# Conn_C.net
KiCad netlist of a schematic drawn in Altium Designer
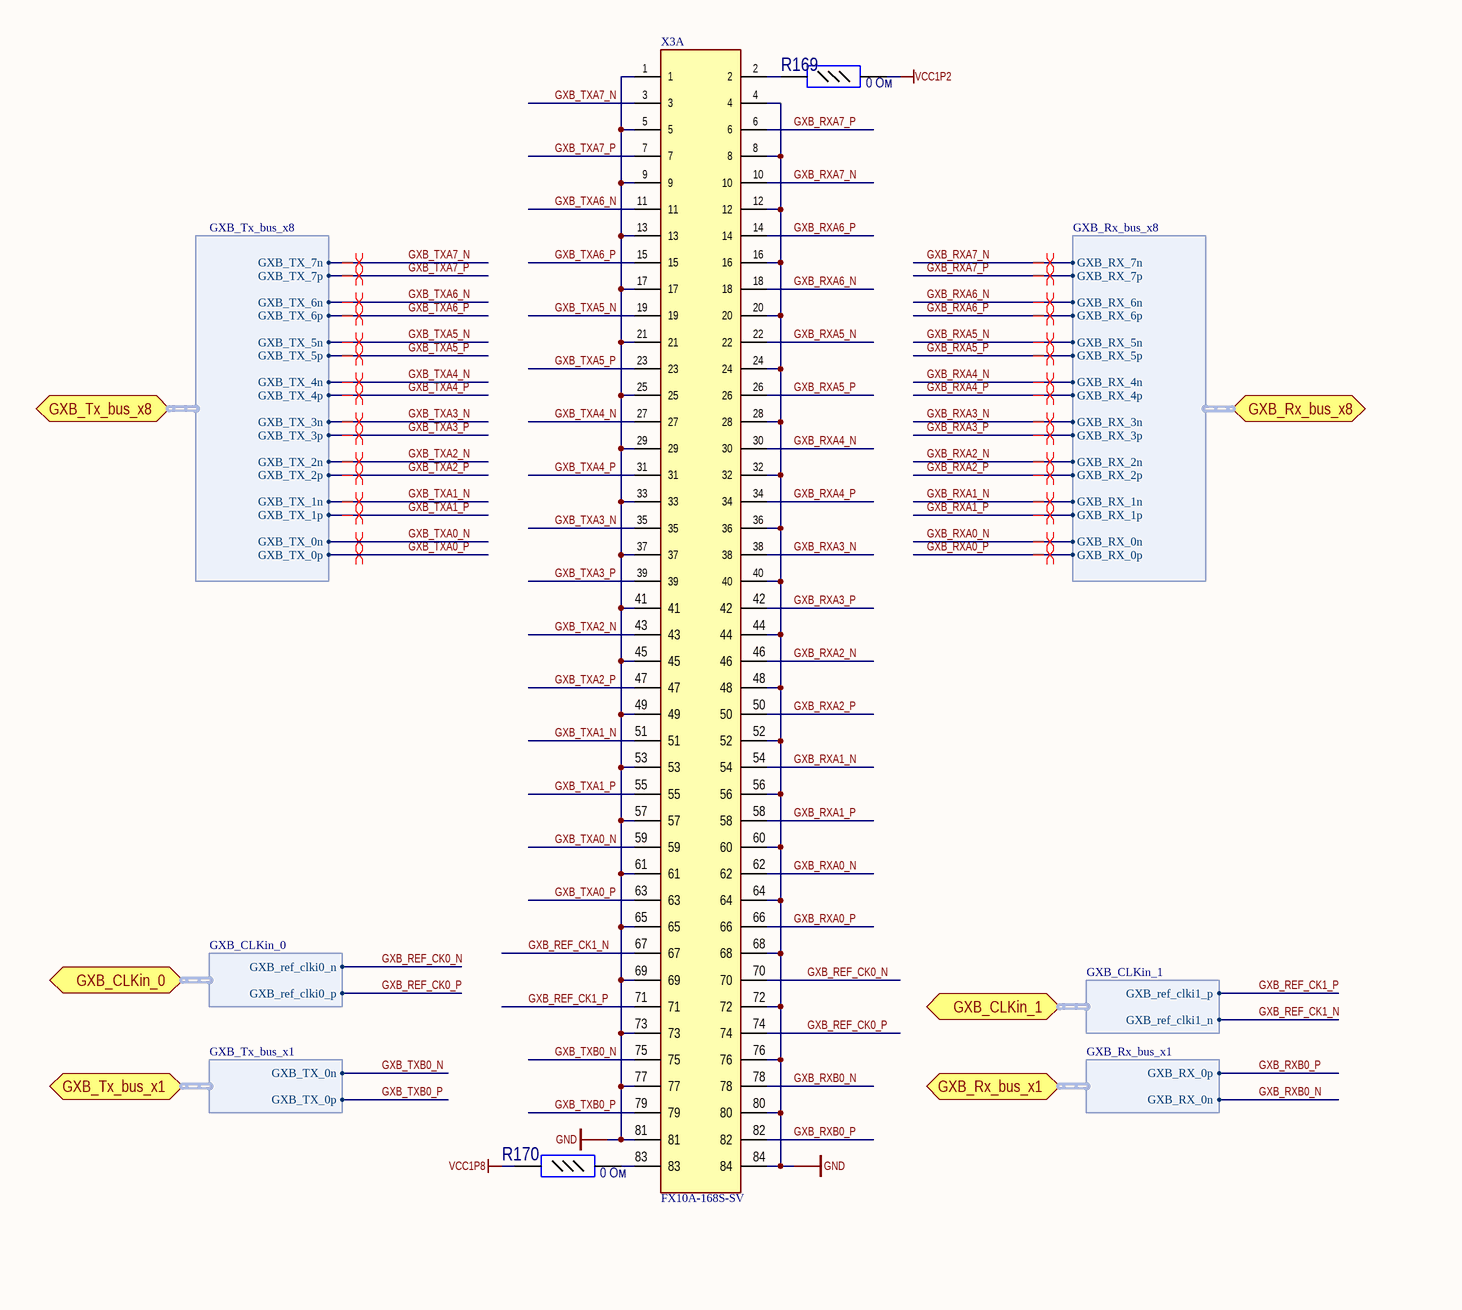
[diagram p0: Conn_C.SchDoc, left]
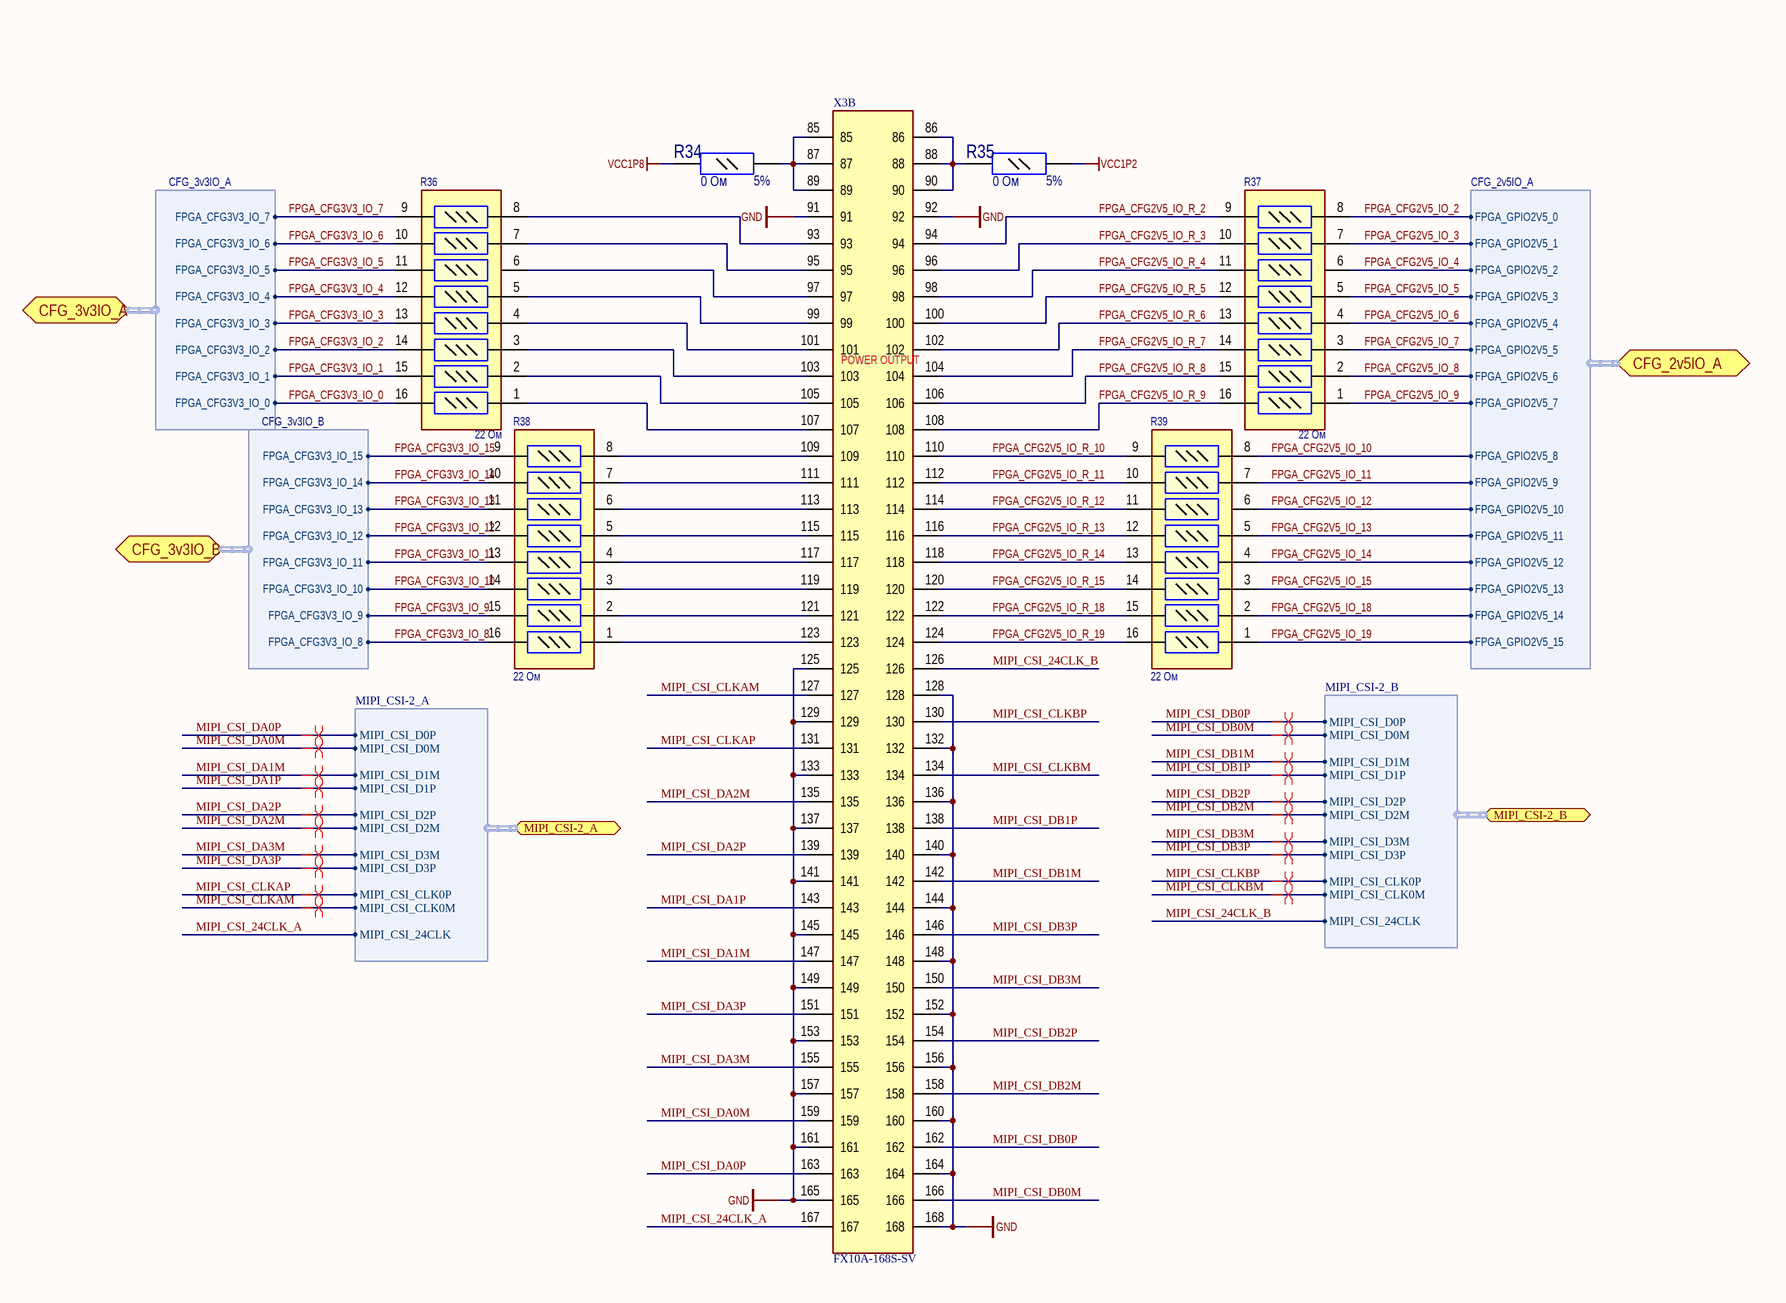
[diagram p1: Conn_C.SchDoc, right]

(export (version "E")
  (design (tool "Eeschema 10.0.6"))
  (components
    (comp (ref "R34")
      (value "0 Ом")
      (footprint "CR0805")
      (description "Чип резистор")
      (fields (field (name "TOLERANCE") "5%") (field (name "Comment") "CR0805-0 Ом-±5%"))
      (libsource (lib "Резисторы") (part "CR0805-#-±1%"))
    )
    (comp (ref "R35")
      (value "0 Ом")
      (footprint "CR0805")
      (description "Чип резистор")
      (fields (field (name "TOLERANCE") "5%") (field (name "Comment") "CR0805-0 Ом-±5%"))
      (libsource (lib "Резисторы") (part "CR0805-#-±1%"))
    )
    (comp (ref "R36")
      (value "22 Ом")
      (footprint "CAT16-J8")
      (description "Набор чип резисторов")
      (fields (field (name "Comment") "YC248-JR-07-22 Ом"))
      (libsource (lib "SD_IC") (part "YC248-JR-07-#"))
    )
    (comp (ref "R37")
      (value "22 Ом")
      (footprint "CAT16-J8")
      (description "Набор чип резисторов")
      (fields (field (name "Comment") "YC248-JR-07-22 Ом"))
      (libsource (lib "SD_IC") (part "YC248-JR-07-#"))
    )
    (comp (ref "R38")
      (value "22 Ом")
      (footprint "CAT16-J8")
      (description "Набор чип резисторов")
      (fields (field (name "Comment") "YC248-JR-07-22 Ом"))
      (libsource (lib "SD_IC") (part "YC248-JR-07-#"))
    )
    (comp (ref "R39")
      (value "22 Ом")
      (footprint "CAT16-J8")
      (description "Набор чип резисторов")
      (fields (field (name "Comment") "YC248-JR-07-22 Ом"))
      (libsource (lib "SD_IC") (part "YC248-JR-07-#"))
    )
    (comp (ref "R169")
      (value "0 Ом")
      (footprint "CR0603")
      (description "Чип резистор")
      (fields (field (name "Comment") "CR0603-0 Ом-±5%"))
      (libsource (lib "Резисторы") (part "CR0603-#-±5%"))
    )
    (comp (ref "R170")
      (value "0 Ом")
      (footprint "CR0603")
      (description "Чип резистор")
      (fields (field (name "Comment") "CR0603-0 Ом-±5%"))
      (libsource (lib "Резисторы") (part "CR0603-#-±5%"))
    )
    (comp (ref "X3")
      (value "FX10A-168S-SV")
      (footprint "FX10A-168S-SV")
      (libsource (lib "SD_IC") (part "FX10A-168S-SV"))
    )
  )
  (nets
    (net (code "12") (name "/FPGA_CFG2V5_IO_2") (class "Default")
      (node (ref "R37") (pin "8") (pintype "passive"))
    )
    (net (code "13") (name "/FPGA_CFG2V5_IO_3") (class "Default")
      (node (ref "R37") (pin "7") (pintype "passive"))
    )
    (net (code "14") (name "/FPGA_CFG2V5_IO_4") (class "Default")
      (node (ref "R37") (pin "6") (pintype "passive"))
    )
    (net (code "15") (name "/FPGA_CFG2V5_IO_5") (class "Default")
      (node (ref "R37") (pin "5") (pintype "passive"))
    )
    (net (code "16") (name "/FPGA_CFG2V5_IO_6") (class "Default")
      (node (ref "R37") (pin "4") (pintype "passive"))
    )
    (net (code "17") (name "/FPGA_CFG2V5_IO_7") (class "Default")
      (node (ref "R37") (pin "3") (pintype "passive"))
    )
    (net (code "18") (name "/FPGA_CFG2V5_IO_8") (class "Default")
      (node (ref "R37") (pin "2") (pintype "passive"))
    )
    (net (code "19") (name "/FPGA_CFG2V5_IO_9") (class "Default")
      (node (ref "R37") (pin "1") (pintype "passive"))
    )
    (net (code "20") (name "/FPGA_CFG2V5_IO_10") (class "Default")
      (node (ref "R39") (pin "8") (pintype "passive"))
    )
    (net (code "21") (name "/FPGA_CFG2V5_IO_11") (class "Default")
      (node (ref "R39") (pin "7") (pintype "passive"))
    )
    (net (code "22") (name "/FPGA_CFG2V5_IO_12") (class "Default")
      (node (ref "R39") (pin "6") (pintype "passive"))
    )
    (net (code "23") (name "/FPGA_CFG2V5_IO_13") (class "Default")
      (node (ref "R39") (pin "5") (pintype "passive"))
    )
    (net (code "24") (name "/FPGA_CFG2V5_IO_14") (class "Default")
      (node (ref "R39") (pin "4") (pintype "passive"))
    )
    (net (code "25") (name "/FPGA_CFG2V5_IO_15") (class "Default")
      (node (ref "R39") (pin "3") (pintype "passive"))
    )
    (net (code "26") (name "/FPGA_CFG2V5_IO_18") (class "Default")
      (node (ref "R39") (pin "2") (pintype "passive"))
    )
    (net (code "27") (name "/FPGA_CFG2V5_IO_19") (class "Default")
      (node (ref "R39") (pin "1") (pintype "passive"))
    )
    (net (code "28") (name "/FPGA_CFG2V5_IO_R_2") (class "Default")
      (node (ref "R37") (pin "9") (pintype "passive"))
      (node (ref "X3") (pin "94") (pinfunction "94_94") (pintype "passive"))
    )
    (net (code "29") (name "/FPGA_CFG2V5_IO_R_3") (class "Default")
      (node (ref "R37") (pin "10") (pintype "passive"))
      (node (ref "X3") (pin "96") (pinfunction "96_96") (pintype "passive"))
    )
    (net (code "30") (name "/FPGA_CFG2V5_IO_R_4") (class "Default")
      (node (ref "R37") (pin "11") (pintype "passive"))
      (node (ref "X3") (pin "98") (pinfunction "98_98") (pintype "passive"))
    )
    (net (code "31") (name "/FPGA_CFG2V5_IO_R_5") (class "Default")
      (node (ref "R37") (pin "12") (pintype "passive"))
      (node (ref "X3") (pin "100") (pinfunction "100_100") (pintype "passive"))
    )
    (net (code "32") (name "/FPGA_CFG2V5_IO_R_6") (class "Default")
      (node (ref "R37") (pin "13") (pintype "passive"))
      (node (ref "X3") (pin "102") (pinfunction "102_102") (pintype "passive"))
    )
    (net (code "33") (name "/FPGA_CFG2V5_IO_R_7") (class "Default")
      (node (ref "R37") (pin "14") (pintype "passive"))
      (node (ref "X3") (pin "104") (pinfunction "104_104") (pintype "passive"))
    )
    (net (code "34") (name "/FPGA_CFG2V5_IO_R_8") (class "Default")
      (node (ref "R37") (pin "15") (pintype "passive"))
      (node (ref "X3") (pin "106") (pinfunction "106_106") (pintype "passive"))
    )
    (net (code "35") (name "/FPGA_CFG2V5_IO_R_9") (class "Default")
      (node (ref "R37") (pin "16") (pintype "passive"))
      (node (ref "X3") (pin "108") (pinfunction "108_108") (pintype "passive"))
    )
    (net (code "36") (name "/FPGA_CFG2V5_IO_R_10") (class "Default")
      (node (ref "R39") (pin "9") (pintype "passive"))
      (node (ref "X3") (pin "110") (pinfunction "110_110") (pintype "passive"))
    )
    (net (code "37") (name "/FPGA_CFG2V5_IO_R_11") (class "Default")
      (node (ref "R39") (pin "10") (pintype "passive"))
      (node (ref "X3") (pin "112") (pinfunction "112_112") (pintype "passive"))
    )
    (net (code "38") (name "/FPGA_CFG2V5_IO_R_12") (class "Default")
      (node (ref "R39") (pin "11") (pintype "passive"))
      (node (ref "X3") (pin "114") (pinfunction "114_114") (pintype "passive"))
    )
    (net (code "39") (name "/FPGA_CFG2V5_IO_R_13") (class "Default")
      (node (ref "R39") (pin "12") (pintype "passive"))
      (node (ref "X3") (pin "116") (pinfunction "116_116") (pintype "passive"))
    )
    (net (code "40") (name "/FPGA_CFG2V5_IO_R_14") (class "Default")
      (node (ref "R39") (pin "13") (pintype "passive"))
      (node (ref "X3") (pin "118") (pinfunction "118_118") (pintype "passive"))
    )
    (net (code "41") (name "/FPGA_CFG2V5_IO_R_15") (class "Default")
      (node (ref "R39") (pin "14") (pintype "passive"))
      (node (ref "X3") (pin "120") (pinfunction "120_120") (pintype "passive"))
    )
    (net (code "42") (name "/FPGA_CFG2V5_IO_R_18") (class "Default")
      (node (ref "R39") (pin "15") (pintype "passive"))
      (node (ref "X3") (pin "122") (pinfunction "122_122") (pintype "passive"))
    )
    (net (code "43") (name "/FPGA_CFG2V5_IO_R_19") (class "Default")
      (node (ref "R39") (pin "16") (pintype "passive"))
      (node (ref "X3") (pin "124") (pinfunction "124_124") (pintype "passive"))
    )
    (net (code "44") (name "/FPGA_CFG3V3_IO_0") (class "Default")
      (node (ref "R36") (pin "16") (pintype "passive"))
    )
    (net (code "45") (name "/FPGA_CFG3V3_IO_1") (class "Default")
      (node (ref "R36") (pin "15") (pintype "passive"))
    )
    (net (code "46") (name "/FPGA_CFG3V3_IO_2") (class "Default")
      (node (ref "R36") (pin "14") (pintype "passive"))
    )
    (net (code "47") (name "/FPGA_CFG3V3_IO_3") (class "Default")
      (node (ref "R36") (pin "13") (pintype "passive"))
    )
    (net (code "48") (name "/FPGA_CFG3V3_IO_4") (class "Default")
      (node (ref "R36") (pin "12") (pintype "passive"))
    )
    (net (code "49") (name "/FPGA_CFG3V3_IO_5") (class "Default")
      (node (ref "R36") (pin "11") (pintype "passive"))
    )
    (net (code "50") (name "/FPGA_CFG3V3_IO_6") (class "Default")
      (node (ref "R36") (pin "10") (pintype "passive"))
    )
    (net (code "51") (name "/FPGA_CFG3V3_IO_7") (class "Default")
      (node (ref "R36") (pin "9") (pintype "passive"))
    )
    (net (code "52") (name "/FPGA_CFG3V3_IO_8") (class "Default")
      (node (ref "R38") (pin "16") (pintype "passive"))
    )
    (net (code "53") (name "/FPGA_CFG3V3_IO_9") (class "Default")
      (node (ref "R38") (pin "15") (pintype "passive"))
    )
    (net (code "54") (name "/FPGA_CFG3V3_IO_10") (class "Default")
      (node (ref "R38") (pin "14") (pintype "passive"))
    )
    (net (code "55") (name "/FPGA_CFG3V3_IO_11") (class "Default")
      (node (ref "R38") (pin "13") (pintype "passive"))
    )
    (net (code "56") (name "/FPGA_CFG3V3_IO_12") (class "Default")
      (node (ref "R38") (pin "12") (pintype "passive"))
    )
    (net (code "57") (name "/FPGA_CFG3V3_IO_13") (class "Default")
      (node (ref "R38") (pin "11") (pintype "passive"))
    )
    (net (code "58") (name "/FPGA_CFG3V3_IO_14") (class "Default")
      (node (ref "R38") (pin "10") (pintype "passive"))
    )
    (net (code "59") (name "/FPGA_CFG3V3_IO_15") (class "Default")
      (node (ref "R38") (pin "9") (pintype "passive"))
    )
    (net (code "60") (name "/GXB_REF_CK0_N") (class "Default")
      (node (ref "X3") (pin "70") (pinfunction "70_70") (pintype "passive"))
    )
    (net (code "61") (name "/GXB_REF_CK0_P") (class "Default")
      (node (ref "X3") (pin "74") (pinfunction "74_74") (pintype "passive"))
    )
    (net (code "62") (name "/GXB_REF_CK1_N") (class "Default")
      (node (ref "X3") (pin "67") (pinfunction "67_67") (pintype "passive"))
    )
    (net (code "63") (name "/GXB_REF_CK1_P") (class "Default")
      (node (ref "X3") (pin "71") (pinfunction "71_71") (pintype "passive"))
    )
    (net (code "64") (name "/GXB_RXA0_N") (class "Default")
      (node (ref "X3") (pin "62") (pinfunction "62_62") (pintype "passive"))
    )
    (net (code "65") (name "/GXB_RXA0_P") (class "Default")
      (node (ref "X3") (pin "66") (pinfunction "66_66") (pintype "passive"))
    )
    (net (code "66") (name "/GXB_RXA1_N") (class "Default")
      (node (ref "X3") (pin "54") (pinfunction "54_54") (pintype "passive"))
    )
    (net (code "67") (name "/GXB_RXA1_P") (class "Default")
      (node (ref "X3") (pin "58") (pinfunction "58_58") (pintype "passive"))
    )
    (net (code "68") (name "/GXB_RXA2_N") (class "Default")
      (node (ref "X3") (pin "46") (pinfunction "46_46") (pintype "passive"))
    )
    (net (code "69") (name "/GXB_RXA2_P") (class "Default")
      (node (ref "X3") (pin "50") (pinfunction "50_50") (pintype "passive"))
    )
    (net (code "70") (name "/GXB_RXA3_N") (class "Default")
      (node (ref "X3") (pin "38") (pinfunction "38_38") (pintype "passive"))
    )
    (net (code "71") (name "/GXB_RXA3_P") (class "Default")
      (node (ref "X3") (pin "42") (pinfunction "42_42") (pintype "passive"))
    )
    (net (code "72") (name "/GXB_RXA4_N") (class "Default")
      (node (ref "X3") (pin "30") (pinfunction "30_30") (pintype "passive"))
    )
    (net (code "73") (name "/GXB_RXA4_P") (class "Default")
      (node (ref "X3") (pin "34") (pinfunction "34_34") (pintype "passive"))
    )
    (net (code "74") (name "/GXB_RXA5_N") (class "Default")
      (node (ref "X3") (pin "22") (pinfunction "22_22") (pintype "passive"))
    )
    (net (code "75") (name "/GXB_RXA5_P") (class "Default")
      (node (ref "X3") (pin "26") (pinfunction "26_26") (pintype "passive"))
    )
    (net (code "76") (name "/GXB_RXA6_N") (class "Default")
      (node (ref "X3") (pin "18") (pinfunction "18_18") (pintype "passive"))
    )
    (net (code "77") (name "/GXB_RXA6_P") (class "Default")
      (node (ref "X3") (pin "14") (pinfunction "14_14") (pintype "passive"))
    )
    (net (code "78") (name "/GXB_RXA7_N") (class "Default")
      (node (ref "X3") (pin "10") (pinfunction "10_10") (pintype "passive"))
    )
    (net (code "79") (name "/GXB_RXA7_P") (class "Default")
      (node (ref "X3") (pin "6") (pinfunction "6_6") (pintype "passive"))
    )
    (net (code "80") (name "/GXB_RXB0_N") (class "Default")
      (node (ref "X3") (pin "78") (pinfunction "78_78") (pintype "passive"))
    )
    (net (code "81") (name "/GXB_RXB0_P") (class "Default")
      (node (ref "X3") (pin "82") (pinfunction "82_82") (pintype "passive"))
    )
    (net (code "82") (name "/GXB_TXA0_N") (class "Default")
      (node (ref "X3") (pin "59") (pinfunction "59_59") (pintype "passive"))
    )
    (net (code "83") (name "/GXB_TXA0_P") (class "Default")
      (node (ref "X3") (pin "63") (pinfunction "63_63") (pintype "passive"))
    )
    (net (code "84") (name "/GXB_TXA1_N") (class "Default")
      (node (ref "X3") (pin "51") (pinfunction "51_51") (pintype "passive"))
    )
    (net (code "85") (name "/GXB_TXA1_P") (class "Default")
      (node (ref "X3") (pin "55") (pinfunction "55_55") (pintype "passive"))
    )
    (net (code "86") (name "/GXB_TXA2_N") (class "Default")
      (node (ref "X3") (pin "43") (pinfunction "43_43") (pintype "passive"))
    )
    (net (code "87") (name "/GXB_TXA2_P") (class "Default")
      (node (ref "X3") (pin "47") (pinfunction "47_47") (pintype "passive"))
    )
    (net (code "88") (name "/GXB_TXA3_N") (class "Default")
      (node (ref "X3") (pin "35") (pinfunction "35_35") (pintype "passive"))
    )
    (net (code "89") (name "/GXB_TXA3_P") (class "Default")
      (node (ref "X3") (pin "39") (pinfunction "39_39") (pintype "passive"))
    )
    (net (code "90") (name "/GXB_TXA4_N") (class "Default")
      (node (ref "X3") (pin "27") (pinfunction "27_27") (pintype "passive"))
    )
    (net (code "91") (name "/GXB_TXA4_P") (class "Default")
      (node (ref "X3") (pin "31") (pinfunction "31_31") (pintype "passive"))
    )
    (net (code "92") (name "/GXB_TXA5_N") (class "Default")
      (node (ref "X3") (pin "19") (pinfunction "19_19") (pintype "passive"))
    )
    (net (code "93") (name "/GXB_TXA5_P") (class "Default")
      (node (ref "X3") (pin "23") (pinfunction "23_23") (pintype "passive"))
    )
    (net (code "94") (name "/GXB_TXA6_N") (class "Default")
      (node (ref "X3") (pin "11") (pinfunction "11_11") (pintype "passive"))
    )
    (net (code "95") (name "/GXB_TXA6_P") (class "Default")
      (node (ref "X3") (pin "15") (pinfunction "15_15") (pintype "passive"))
    )
    (net (code "96") (name "/GXB_TXA7_N") (class "Default")
      (node (ref "X3") (pin "3") (pinfunction "3_3") (pintype "passive"))
    )
    (net (code "97") (name "/GXB_TXA7_P") (class "Default")
      (node (ref "X3") (pin "7") (pinfunction "7_7") (pintype "passive"))
    )
    (net (code "98") (name "/GXB_TXB0_N") (class "Default")
      (node (ref "X3") (pin "75") (pinfunction "75_75") (pintype "passive"))
    )
    (net (code "99") (name "/GXB_TXB0_P") (class "Default")
      (node (ref "X3") (pin "79") (pinfunction "79_79") (pintype "passive"))
    )
    (net (code "100") (name "/MIPI_CSI_24CLK_A") (class "Default")
      (node (ref "X3") (pin "167") (pinfunction "167_167") (pintype "passive"))
    )
    (net (code "101") (name "/MIPI_CSI_24CLK_B") (class "Default")
      (node (ref "X3") (pin "126") (pinfunction "126_126") (pintype "passive"))
    )
    (net (code "102") (name "/MIPI_CSI_CLKAM") (class "Default")
      (node (ref "X3") (pin "127") (pinfunction "127_127") (pintype "passive"))
    )
    (net (code "103") (name "/MIPI_CSI_CLKAP") (class "Default")
      (node (ref "X3") (pin "131") (pinfunction "131_131") (pintype "passive"))
    )
    (net (code "104") (name "/MIPI_CSI_CLKBM") (class "Default")
      (node (ref "X3") (pin "134") (pinfunction "134_134") (pintype "passive"))
    )
    (net (code "105") (name "/MIPI_CSI_CLKBP") (class "Default")
      (node (ref "X3") (pin "130") (pinfunction "130_130") (pintype "passive"))
    )
    (net (code "106") (name "/MIPI_CSI_DA0M") (class "Default")
      (node (ref "X3") (pin "159") (pinfunction "159_159") (pintype "passive"))
    )
    (net (code "107") (name "/MIPI_CSI_DA0P") (class "Default")
      (node (ref "X3") (pin "163") (pinfunction "163_163") (pintype "passive"))
    )
    (net (code "108") (name "/MIPI_CSI_DA1M") (class "Default")
      (node (ref "X3") (pin "147") (pinfunction "147_147") (pintype "passive"))
    )
    (net (code "109") (name "/MIPI_CSI_DA1P") (class "Default")
      (node (ref "X3") (pin "143") (pinfunction "143_143") (pintype "passive"))
    )
    (net (code "110") (name "/MIPI_CSI_DA2M") (class "Default")
      (node (ref "X3") (pin "135") (pinfunction "135_135") (pintype "passive"))
    )
    (net (code "111") (name "/MIPI_CSI_DA2P") (class "Default")
      (node (ref "X3") (pin "139") (pinfunction "139_139") (pintype "passive"))
    )
    (net (code "112") (name "/MIPI_CSI_DA3M") (class "Default")
      (node (ref "X3") (pin "155") (pinfunction "155_155") (pintype "passive"))
    )
    (net (code "113") (name "/MIPI_CSI_DA3P") (class "Default")
      (node (ref "X3") (pin "151") (pinfunction "151_151") (pintype "passive"))
    )
    (net (code "114") (name "/MIPI_CSI_DB0M") (class "Default")
      (node (ref "X3") (pin "166") (pinfunction "166_166") (pintype "passive"))
    )
    (net (code "115") (name "/MIPI_CSI_DB0P") (class "Default")
      (node (ref "X3") (pin "162") (pinfunction "162_162") (pintype "passive"))
    )
    (net (code "116") (name "/MIPI_CSI_DB1M") (class "Default")
      (node (ref "X3") (pin "142") (pinfunction "142_142") (pintype "passive"))
    )
    (net (code "117") (name "/MIPI_CSI_DB1P") (class "Default")
      (node (ref "X3") (pin "138") (pinfunction "138_138") (pintype "passive"))
    )
    (net (code "118") (name "/MIPI_CSI_DB2M") (class "Default")
      (node (ref "X3") (pin "158") (pinfunction "158_158") (pintype "passive"))
    )
    (net (code "119") (name "/MIPI_CSI_DB2P") (class "Default")
      (node (ref "X3") (pin "154") (pinfunction "154_154") (pintype "passive"))
    )
    (net (code "120") (name "/MIPI_CSI_DB3M") (class "Default")
      (node (ref "X3") (pin "150") (pinfunction "150_150") (pintype "passive"))
    )
    (net (code "121") (name "/MIPI_CSI_DB3P") (class "Default")
      (node (ref "X3") (pin "146") (pinfunction "146_146") (pintype "passive"))
    )
    (net (code "133") (name "GND") (class "Default")
      (node (ref "X3") (pin "1") (pinfunction "1_1") (pintype "passive"))
      (node (ref "X3") (pin "12") (pinfunction "12_12") (pintype "passive"))
      (node (ref "X3") (pin "125") (pinfunction "125_125") (pintype "passive"))
      (node (ref "X3") (pin "128") (pinfunction "128_128") (pintype "passive"))
      (node (ref "X3") (pin "129") (pinfunction "129_129") (pintype "passive"))
      (node (ref "X3") (pin "13") (pinfunction "13_13") (pintype "passive"))
      (node (ref "X3") (pin "132") (pinfunction "132_132") (pintype "passive"))
      (node (ref "X3") (pin "133") (pinfunction "133_133") (pintype "passive"))
      (node (ref "X3") (pin "136") (pinfunction "136_136") (pintype "passive"))
      (node (ref "X3") (pin "137") (pinfunction "137_137") (pintype "passive"))
      (node (ref "X3") (pin "140") (pinfunction "140_140") (pintype "passive"))
      (node (ref "X3") (pin "141") (pinfunction "141_141") (pintype "passive"))
      (node (ref "X3") (pin "144") (pinfunction "144_144") (pintype "passive"))
      (node (ref "X3") (pin "145") (pinfunction "145_145") (pintype "passive"))
      (node (ref "X3") (pin "148") (pinfunction "148_148") (pintype "passive"))
      (node (ref "X3") (pin "149") (pinfunction "149_149") (pintype "passive"))
      (node (ref "X3") (pin "152") (pinfunction "152_152") (pintype "passive"))
      (node (ref "X3") (pin "153") (pinfunction "153_153") (pintype "passive"))
      (node (ref "X3") (pin "156") (pinfunction "156_156") (pintype "passive"))
      (node (ref "X3") (pin "157") (pinfunction "157_157") (pintype "passive"))
      (node (ref "X3") (pin "16") (pinfunction "16_16") (pintype "passive"))
      (node (ref "X3") (pin "160") (pinfunction "160_160") (pintype "passive"))
      (node (ref "X3") (pin "161") (pinfunction "161_161") (pintype "passive"))
      (node (ref "X3") (pin "164") (pinfunction "164_164") (pintype "passive"))
      (node (ref "X3") (pin "165") (pinfunction "165_165") (pintype "passive"))
      (node (ref "X3") (pin "168") (pinfunction "168_168") (pintype "passive"))
      (node (ref "X3") (pin "17") (pinfunction "17_17") (pintype "passive"))
      (node (ref "X3") (pin "20") (pinfunction "20_20") (pintype "passive"))
      (node (ref "X3") (pin "21") (pinfunction "21_21") (pintype "passive"))
      (node (ref "X3") (pin "24") (pinfunction "24_24") (pintype "passive"))
      (node (ref "X3") (pin "25") (pinfunction "25_25") (pintype "passive"))
      (node (ref "X3") (pin "28") (pinfunction "28_28") (pintype "passive"))
      (node (ref "X3") (pin "29") (pinfunction "29_29") (pintype "passive"))
      (node (ref "X3") (pin "32") (pinfunction "32_32") (pintype "passive"))
      (node (ref "X3") (pin "33") (pinfunction "33_33") (pintype "passive"))
      (node (ref "X3") (pin "36") (pinfunction "36_36") (pintype "passive"))
      (node (ref "X3") (pin "37") (pinfunction "37_37") (pintype "passive"))
      (node (ref "X3") (pin "4") (pinfunction "4_4") (pintype "passive"))
      (node (ref "X3") (pin "40") (pinfunction "40_40") (pintype "passive"))
      (node (ref "X3") (pin "41") (pinfunction "41_41") (pintype "passive"))
      (node (ref "X3") (pin "44") (pinfunction "44_44") (pintype "passive"))
      (node (ref "X3") (pin "45") (pinfunction "45_45") (pintype "passive"))
      (node (ref "X3") (pin "48") (pinfunction "48_48") (pintype "passive"))
      (node (ref "X3") (pin "49") (pinfunction "49_49") (pintype "passive"))
      (node (ref "X3") (pin "5") (pinfunction "5_5") (pintype "passive"))
      (node (ref "X3") (pin "52") (pinfunction "52_52") (pintype "passive"))
      (node (ref "X3") (pin "53") (pinfunction "53_53") (pintype "passive"))
      (node (ref "X3") (pin "56") (pinfunction "56_56") (pintype "passive"))
      (node (ref "X3") (pin "57") (pinfunction "57_57") (pintype "passive"))
      (node (ref "X3") (pin "60") (pinfunction "60_60") (pintype "passive"))
      (node (ref "X3") (pin "61") (pinfunction "61_61") (pintype "passive"))
      (node (ref "X3") (pin "64") (pinfunction "64_64") (pintype "passive"))
      (node (ref "X3") (pin "65") (pinfunction "65_65") (pintype "passive"))
      (node (ref "X3") (pin "68") (pinfunction "68_68") (pintype "passive"))
      (node (ref "X3") (pin "69") (pinfunction "69_69") (pintype "passive"))
      (node (ref "X3") (pin "72") (pinfunction "72_72") (pintype "passive"))
      (node (ref "X3") (pin "73") (pinfunction "73_73") (pintype "passive"))
      (node (ref "X3") (pin "76") (pinfunction "76_76") (pintype "passive"))
      (node (ref "X3") (pin "77") (pinfunction "77_77") (pintype "passive"))
      (node (ref "X3") (pin "8") (pinfunction "8_8") (pintype "passive"))
      (node (ref "X3") (pin "80") (pinfunction "80_80") (pintype "passive"))
      (node (ref "X3") (pin "81") (pinfunction "81_81") (pintype "passive"))
      (node (ref "X3") (pin "84") (pinfunction "84_84") (pintype "passive"))
      (node (ref "X3") (pin "9") (pinfunction "9_9") (pintype "passive"))
      (node (ref "X3") (pin "91") (pinfunction "91_91") (pintype "passive"))
      (node (ref "X3") (pin "92") (pinfunction "92_92") (pintype "passive"))
    )
    (net (code "134") (name "Net-(R34--)") (class "Default")
      (node (ref "R34") (pin "2") (pinfunction "-_2") (pintype "passive"))
      (node (ref "X3") (pin "85") (pinfunction "85_85") (pintype "passive"))
      (node (ref "X3") (pin "87") (pinfunction "87_87") (pintype "passive"))
      (node (ref "X3") (pin "89") (pinfunction "89_89") (pintype "passive"))
    )
    (net (code "135") (name "Net-(R35-+)") (class "Default")
      (node (ref "R35") (pin "1") (pinfunction "+_1") (pintype "passive"))
      (node (ref "X3") (pin "86") (pinfunction "86_86") (pintype "passive"))
      (node (ref "X3") (pin "88") (pinfunction "88_88") (pintype "passive"))
      (node (ref "X3") (pin "90") (pinfunction "90_90") (pintype "passive"))
    )
    (net (code "136") (name "Net-(R36-Pad1)") (class "Default")
      (node (ref "R36") (pin "1") (pintype "passive"))
      (node (ref "X3") (pin "107") (pinfunction "107_107") (pintype "passive"))
    )
    (net (code "137") (name "Net-(R36-Pad2)") (class "Default")
      (node (ref "R36") (pin "2") (pintype "passive"))
      (node (ref "X3") (pin "105") (pinfunction "105_105") (pintype "passive"))
    )
    (net (code "138") (name "Net-(R36-Pad3)") (class "Default")
      (node (ref "R36") (pin "3") (pintype "passive"))
      (node (ref "X3") (pin "103") (pinfunction "103_103") (pintype "passive"))
    )
    (net (code "139") (name "Net-(R36-Pad4)") (class "Default")
      (node (ref "R36") (pin "4") (pintype "passive"))
      (node (ref "X3") (pin "101") (pinfunction "101_101") (pintype "passive"))
    )
    (net (code "140") (name "Net-(R36-Pad5)") (class "Default")
      (node (ref "R36") (pin "5") (pintype "passive"))
      (node (ref "X3") (pin "99") (pinfunction "99_99") (pintype "passive"))
    )
    (net (code "141") (name "Net-(R36-Pad6)") (class "Default")
      (node (ref "R36") (pin "6") (pintype "passive"))
      (node (ref "X3") (pin "97") (pinfunction "97_97") (pintype "passive"))
    )
    (net (code "142") (name "Net-(R36-Pad7)") (class "Default")
      (node (ref "R36") (pin "7") (pintype "passive"))
      (node (ref "X3") (pin "95") (pinfunction "95_95") (pintype "passive"))
    )
    (net (code "143") (name "Net-(R36-Pad8)") (class "Default")
      (node (ref "R36") (pin "8") (pintype "passive"))
      (node (ref "X3") (pin "93") (pinfunction "93_93") (pintype "passive"))
    )
    (net (code "144") (name "Net-(R38-Pad1)") (class "Default")
      (node (ref "R38") (pin "1") (pintype "passive"))
      (node (ref "X3") (pin "123") (pinfunction "123_123") (pintype "passive"))
    )
    (net (code "145") (name "Net-(R38-Pad2)") (class "Default")
      (node (ref "R38") (pin "2") (pintype "passive"))
      (node (ref "X3") (pin "121") (pinfunction "121_121") (pintype "passive"))
    )
    (net (code "146") (name "Net-(R38-Pad3)") (class "Default")
      (node (ref "R38") (pin "3") (pintype "passive"))
      (node (ref "X3") (pin "119") (pinfunction "119_119") (pintype "passive"))
    )
    (net (code "147") (name "Net-(R38-Pad4)") (class "Default")
      (node (ref "R38") (pin "4") (pintype "passive"))
      (node (ref "X3") (pin "117") (pinfunction "117_117") (pintype "passive"))
    )
    (net (code "148") (name "Net-(R38-Pad5)") (class "Default")
      (node (ref "R38") (pin "5") (pintype "passive"))
      (node (ref "X3") (pin "115") (pinfunction "115_115") (pintype "passive"))
    )
    (net (code "149") (name "Net-(R38-Pad6)") (class "Default")
      (node (ref "R38") (pin "6") (pintype "passive"))
      (node (ref "X3") (pin "113") (pinfunction "113_113") (pintype "passive"))
    )
    (net (code "150") (name "Net-(R38-Pad7)") (class "Default")
      (node (ref "R38") (pin "7") (pintype "passive"))
      (node (ref "X3") (pin "111") (pinfunction "111_111") (pintype "passive"))
    )
    (net (code "151") (name "Net-(R38-Pad8)") (class "Default")
      (node (ref "R38") (pin "8") (pintype "passive"))
      (node (ref "X3") (pin "109") (pinfunction "109_109") (pintype "passive"))
    )
    (net (code "152") (name "Net-(R169-+)") (class "Default")
      (node (ref "R169") (pin "1") (pinfunction "+_1") (pintype "passive"))
      (node (ref "X3") (pin "2") (pinfunction "2_2") (pintype "passive"))
    )
    (net (code "153") (name "Net-(R170--)") (class "Default")
      (node (ref "R170") (pin "2") (pinfunction "-_2") (pintype "passive"))
      (node (ref "X3") (pin "83") (pinfunction "83_83") (pintype "passive"))
    )
    (net (code "154") (name "VCC1P2") (class "Default")
      (node (ref "R169") (pin "2") (pinfunction "-_2") (pintype "passive"))
      (node (ref "R35") (pin "2") (pinfunction "-_2") (pintype "passive"))
    )
    (net (code "155") (name "VCC1P8") (class "Default")
      (node (ref "R170") (pin "1") (pinfunction "+_1") (pintype "passive"))
      (node (ref "R34") (pin "1") (pinfunction "+_1") (pintype "passive"))
    )
  )
)
